# Hub.net
KiCad netlist of a schematic drawn in EAGLE
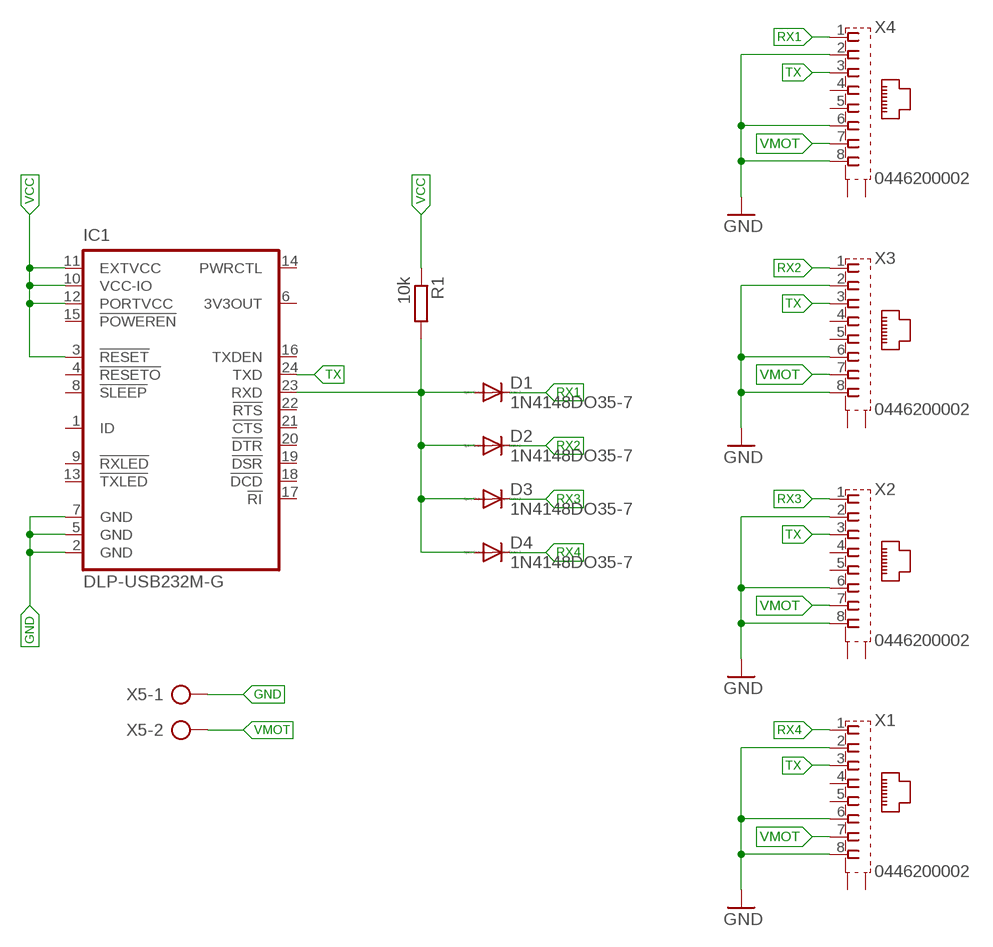
[diagram p0: schematic, sheet 1]

(export (version "E")
  (design (tool "Eeschema 10.0.6"))
  (components
    (comp (ref "D1")
      (value "1N4148DO35-7")
      (footprint "eagle-import:DO35-7")
      (libsource (lib "eagle-import") (part "1N4148DO35-7"))
    )
    (comp (ref "D2")
      (value "1N4148DO35-7")
      (footprint "eagle-import:DO35-7")
      (libsource (lib "eagle-import") (part "1N4148DO35-7"))
    )
    (comp (ref "D3")
      (value "1N4148DO35-7")
      (footprint "eagle-import:DO35-7")
      (libsource (lib "eagle-import") (part "1N4148DO35-7"))
    )
    (comp (ref "D4")
      (value "1N4148DO35-7")
      (footprint "eagle-import:DO35-7")
      (libsource (lib "eagle-import") (part "1N4148DO35-7"))
    )
    (comp (ref "IC1")
      (value "DLP-USB232M-G")
      (footprint "eagle-import:DLP-USB232M")
      (libsource (lib "eagle-import") (part "DLP-USB232M-G"))
    )
    (comp (ref "R1")
      (value "10k")
      (footprint "eagle-import:0204_7")
      (libsource (lib "eagle-import") (part "R-EU_0204/7"))
    )
    (comp (ref "X1")
      (value "0446200002")
      (footprint "eagle-import:0446200002")
      (fields (field (name "MF") "MOLEX"))
      (libsource (lib "eagle-import") (part "0446200002"))
    )
    (comp (ref "X2")
      (value "0446200002")
      (footprint "eagle-import:0446200002")
      (fields (field (name "MF") "MOLEX"))
      (libsource (lib "eagle-import") (part "0446200002"))
    )
    (comp (ref "X3")
      (value "0446200002")
      (footprint "eagle-import:0446200002")
      (fields (field (name "MF") "MOLEX"))
      (libsource (lib "eagle-import") (part "0446200002"))
    )
    (comp (ref "X4")
      (value "0446200002")
      (footprint "eagle-import:0446200002")
      (fields (field (name "MF") "MOLEX"))
      (libsource (lib "eagle-import") (part "0446200002"))
    )
    (comp (ref "X5")
      (value "AK500/2")
      (footprint "eagle-import:AK500_2")
      (libsource (lib "eagle-import") (part "AK500/2"))
    )
  )
  (nets
    (net (code "1") (name "GND") (class "Default")
      (node (ref "IC1") (pin "2") (pinfunction "GND_2") (pintype "input"))
      (node (ref "IC1") (pin "5") (pinfunction "GND_5") (pintype "input"))
      (node (ref "IC1") (pin "7") (pinfunction "GND_7") (pintype "input"))
      (node (ref "X1") (pin "2") (pinfunction "2_2") (pintype "passive"))
      (node (ref "X1") (pin "6") (pinfunction "6_6") (pintype "passive"))
      (node (ref "X1") (pin "8") (pinfunction "8_8") (pintype "passive"))
      (node (ref "X2") (pin "2") (pinfunction "2_2") (pintype "passive"))
      (node (ref "X2") (pin "6") (pinfunction "6_6") (pintype "passive"))
      (node (ref "X2") (pin "8") (pinfunction "8_8") (pintype "passive"))
      (node (ref "X3") (pin "2") (pinfunction "2_2") (pintype "passive"))
      (node (ref "X3") (pin "6") (pinfunction "6_6") (pintype "passive"))
      (node (ref "X3") (pin "8") (pinfunction "8_8") (pintype "passive"))
      (node (ref "X4") (pin "2") (pinfunction "2_2") (pintype "passive"))
      (node (ref "X4") (pin "6") (pinfunction "6_6") (pintype "passive"))
      (node (ref "X4") (pin "8") (pinfunction "8_8") (pintype "passive"))
      (node (ref "X5") (pin "1") (pinfunction "KL_1") (pintype "passive"))
    )
    (net (code "2") (name "Net-(IC1-RXD)") (class "Default")
      (node (ref "D1") (pin "A") (pinfunction "A_A") (pintype "passive"))
      (node (ref "D2") (pin "A") (pinfunction "A_A") (pintype "passive"))
      (node (ref "D3") (pin "A") (pinfunction "A_A") (pintype "passive"))
      (node (ref "D4") (pin "A") (pinfunction "A_A") (pintype "passive"))
      (node (ref "IC1") (pin "23") (pinfunction "RXD_23") (pintype "input"))
      (node (ref "R1") (pin "2") (pinfunction "2_2") (pintype "passive"))
    )
    (net (code "3") (name "RX1") (class "Default")
      (node (ref "D1") (pin "C") (pinfunction "C_C") (pintype "passive"))
      (node (ref "X4") (pin "1") (pinfunction "1_1") (pintype "passive"))
    )
    (net (code "4") (name "RX2") (class "Default")
      (node (ref "D2") (pin "C") (pinfunction "C_C") (pintype "passive"))
      (node (ref "X3") (pin "1") (pinfunction "1_1") (pintype "passive"))
    )
    (net (code "5") (name "RX3") (class "Default")
      (node (ref "D3") (pin "C") (pinfunction "C_C") (pintype "passive"))
      (node (ref "X2") (pin "1") (pinfunction "1_1") (pintype "passive"))
    )
    (net (code "6") (name "RX4") (class "Default")
      (node (ref "D4") (pin "C") (pinfunction "C_C") (pintype "passive"))
      (node (ref "X1") (pin "1") (pinfunction "1_1") (pintype "passive"))
    )
    (net (code "7") (name "TX") (class "Default")
      (node (ref "IC1") (pin "24") (pinfunction "TXD_24") (pintype "input"))
      (node (ref "X1") (pin "3") (pinfunction "3_3") (pintype "passive"))
      (node (ref "X2") (pin "3") (pinfunction "3_3") (pintype "passive"))
      (node (ref "X3") (pin "3") (pinfunction "3_3") (pintype "passive"))
      (node (ref "X4") (pin "3") (pinfunction "3_3") (pintype "passive"))
    )
    (net (code "8") (name "VCC") (class "Default")
      (node (ref "IC1") (pin "10") (pinfunction "VCC-IO_10") (pintype "input"))
      (node (ref "IC1") (pin "11") (pinfunction "EXTVCC_11") (pintype "input"))
      (node (ref "IC1") (pin "12") (pinfunction "PORTVCC_12") (pintype "input"))
      (node (ref "IC1") (pin "3") (pinfunction "~{RESET}_3") (pintype "input"))
      (node (ref "R1") (pin "1") (pinfunction "1_1") (pintype "passive"))
    )
    (net (code "9") (name "VMOT") (class "Default")
      (node (ref "X1") (pin "7") (pinfunction "7_7") (pintype "passive"))
      (node (ref "X2") (pin "7") (pinfunction "7_7") (pintype "passive"))
      (node (ref "X3") (pin "7") (pinfunction "7_7") (pintype "passive"))
      (node (ref "X4") (pin "7") (pinfunction "7_7") (pintype "passive"))
      (node (ref "X5") (pin "2") (pinfunction "KL_2") (pintype "passive"))
    )
    (net (code "10") (name "unconnected-(IC1-3V3OUT-Pad6)") (class "Default")
      (node (ref "IC1") (pin "6") (pinfunction "3V3OUT_6") (pintype "input"))
    )
    (net (code "11") (name "unconnected-(IC1-ID-Pad1)") (class "Default")
      (node (ref "IC1") (pin "1") (pinfunction "ID_1") (pintype "input"))
    )
    (net (code "12") (name "unconnected-(IC1-PWRCTL-Pad14)") (class "Default")
      (node (ref "IC1") (pin "14") (pinfunction "PWRCTL_14") (pintype "input"))
    )
    (net (code "13") (name "unconnected-(IC1-TXDEN-Pad16)") (class "Default")
      (node (ref "IC1") (pin "16") (pinfunction "TXDEN_16") (pintype "input"))
    )
    (net (code "14") (name "unconnected-(IC1-~{CTS}-Pad21)") (class "Default")
      (node (ref "IC1") (pin "21") (pinfunction "~{CTS}_21") (pintype "input"))
    )
    (net (code "15") (name "unconnected-(IC1-~{DCD}-Pad18)") (class "Default")
      (node (ref "IC1") (pin "18") (pinfunction "~{DCD}_18") (pintype "input"))
    )
    (net (code "16") (name "unconnected-(IC1-~{DSR}-Pad19)") (class "Default")
      (node (ref "IC1") (pin "19") (pinfunction "~{DSR}_19") (pintype "input"))
    )
    (net (code "17") (name "unconnected-(IC1-~{DTR}-Pad20)") (class "Default")
      (node (ref "IC1") (pin "20") (pinfunction "~{DTR}_20") (pintype "input"))
    )
    (net (code "18") (name "unconnected-(IC1-~{POWEREN}-Pad15)") (class "Default")
      (node (ref "IC1") (pin "15") (pinfunction "~{POWEREN}_15") (pintype "input"))
    )
    (net (code "19") (name "unconnected-(IC1-~{RESETO}-Pad4)") (class "Default")
      (node (ref "IC1") (pin "4") (pinfunction "~{RESETO}_4") (pintype "input"))
    )
    (net (code "20") (name "unconnected-(IC1-~{RI}-Pad17)") (class "Default")
      (node (ref "IC1") (pin "17") (pinfunction "~{RI}_17") (pintype "input"))
    )
    (net (code "21") (name "unconnected-(IC1-~{RTS}-Pad22)") (class "Default")
      (node (ref "IC1") (pin "22") (pinfunction "~{RTS}_22") (pintype "input"))
    )
    (net (code "22") (name "unconnected-(IC1-~{RXLED}-Pad9)") (class "Default")
      (node (ref "IC1") (pin "9") (pinfunction "~{RXLED}_9") (pintype "input"))
    )
    (net (code "23") (name "unconnected-(IC1-~{SLEEP}-Pad8)") (class "Default")
      (node (ref "IC1") (pin "8") (pinfunction "~{SLEEP}_8") (pintype "input"))
    )
    (net (code "24") (name "unconnected-(IC1-~{TXLED}-Pad13)") (class "Default")
      (node (ref "IC1") (pin "13") (pinfunction "~{TXLED}_13") (pintype "input"))
    )
    (net (code "25") (name "unconnected-(X1-Pad4)") (class "Default")
      (node (ref "X1") (pin "4") (pinfunction "4_4") (pintype "passive"))
    )
    (net (code "26") (name "unconnected-(X1-Pad5)") (class "Default")
      (node (ref "X1") (pin "5") (pinfunction "5_5") (pintype "passive"))
    )
    (net (code "27") (name "unconnected-(X1-S1-PadS@1)") (class "Default")
      (node (ref "X1") (pin "S@1") (pinfunction "S1_S@1") (pintype "passive"))
    )
    (net (code "28") (name "unconnected-(X1-S2-PadS@2)") (class "Default")
      (node (ref "X1") (pin "S@2") (pinfunction "S2_S@2") (pintype "passive"))
    )
    (net (code "29") (name "unconnected-(X2-Pad4)") (class "Default")
      (node (ref "X2") (pin "4") (pinfunction "4_4") (pintype "passive"))
    )
    (net (code "30") (name "unconnected-(X2-Pad5)") (class "Default")
      (node (ref "X2") (pin "5") (pinfunction "5_5") (pintype "passive"))
    )
    (net (code "31") (name "unconnected-(X2-S1-PadS@1)") (class "Default")
      (node (ref "X2") (pin "S@1") (pinfunction "S1_S@1") (pintype "passive"))
    )
    (net (code "32") (name "unconnected-(X2-S2-PadS@2)") (class "Default")
      (node (ref "X2") (pin "S@2") (pinfunction "S2_S@2") (pintype "passive"))
    )
    (net (code "33") (name "unconnected-(X3-Pad4)") (class "Default")
      (node (ref "X3") (pin "4") (pinfunction "4_4") (pintype "passive"))
    )
    (net (code "34") (name "unconnected-(X3-Pad5)") (class "Default")
      (node (ref "X3") (pin "5") (pinfunction "5_5") (pintype "passive"))
    )
    (net (code "35") (name "unconnected-(X3-S1-PadS@1)") (class "Default")
      (node (ref "X3") (pin "S@1") (pinfunction "S1_S@1") (pintype "passive"))
    )
    (net (code "36") (name "unconnected-(X3-S2-PadS@2)") (class "Default")
      (node (ref "X3") (pin "S@2") (pinfunction "S2_S@2") (pintype "passive"))
    )
    (net (code "37") (name "unconnected-(X4-Pad4)") (class "Default")
      (node (ref "X4") (pin "4") (pinfunction "4_4") (pintype "passive"))
    )
    (net (code "38") (name "unconnected-(X4-Pad5)") (class "Default")
      (node (ref "X4") (pin "5") (pinfunction "5_5") (pintype "passive"))
    )
    (net (code "39") (name "unconnected-(X4-S1-PadS@1)") (class "Default")
      (node (ref "X4") (pin "S@1") (pinfunction "S1_S@1") (pintype "passive"))
    )
    (net (code "40") (name "unconnected-(X4-S2-PadS@2)") (class "Default")
      (node (ref "X4") (pin "S@2") (pinfunction "S2_S@2") (pintype "passive"))
    )
  )
)
